# Power.net
KiCad netlist of a schematic drawn in Altium Designer
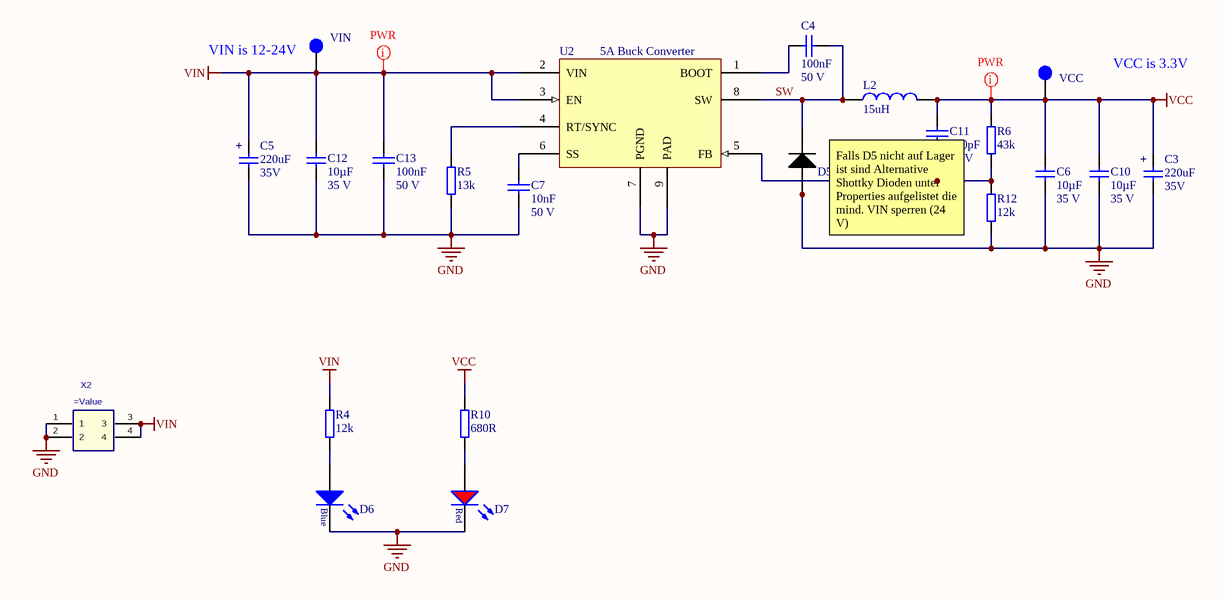
[diagram p0: Power.SchDoc]

(export (version "E")
  (design (tool "Eeschema 10.0.6"))
  (components
    (comp (ref "C3")
      (value "220uF")
      (footprint "CAPAE9083X105M")
      (description "ALUMINUM ELECTROLYTIC CAPACITOR")
      (fields
        (field (name "TOLERANCE") "20%")
        (field (name "LCSC PART #") "C311611")
        (field (name "VOLTAGE") "35V")
        (field (name "CREATED") "2018_06_25_AGeiger")
      )
      (libsource (lib "UZOhm_Optical") (part "C_ELKO_8x10"))
    )
    (comp (ref "C4")
      (value "100nF")
      (footprint "C_0603(1608)100_L")
      (description "CAP 0603 (1608 Metric) SMD")
      (fields
        (field (name "TOLERANCE") "±5%")
        (field (name "LCSC PART #") "C14663")
        (field (name "RATED VOLTAGE") "50 V")
        (field (name "CREATED") "2018_09_06_AGeiger")
      )
      (libsource (lib "UZOhm_Optical") (part "C_0603"))
    )
    (comp (ref "C5")
      (value "220uF")
      (footprint "CAPAE9083X105M")
      (description "ALUMINUM ELECTROLYTIC CAPACITOR")
      (fields
        (field (name "TOLERANCE") "20%")
        (field (name "LCSC PART #") "C311611")
        (field (name "VOLTAGE") "35V")
        (field (name "CREATED") "2018_06_25_AGeiger")
      )
      (libsource (lib "UZOhm_Optical") (part "C_ELKO_8x10"))
    )
    (comp (ref "C6")
      (value "10µF")
      (footprint "C_1206")
      (description "Capacitor 1206")
      (fields
        (field (name "TOLERANCE") "10%")
        (field (name "MF") "Taiyo Yuden")
        (field (name "VOLTAGE") "35 V")
        (field (name "CREATED") "2018_06_25_AGeiger")
      )
      (libsource (lib "UZOhm_Optical") (part "C_1206"))
    )
    (comp (ref "C7")
      (value "10nF")
      (footprint "C_0603(1608)100_L")
      (description "CAP 0603 (1608 Metric) SMD")
      (fields
        (field (name "TOLERANCE") "±5%")
        (field (name "LCSC PART #") "C57112")
        (field (name "RATED VOLTAGE") "50 V")
        (field (name "CREATED") "2018_09_06_AGeiger")
      )
      (libsource (lib "UZOhm_Optical") (part "C_0603"))
    )
    (comp (ref "C10")
      (value "10µF")
      (footprint "C_1206")
      (description "Capacitor 1206")
      (fields
        (field (name "TOLERANCE") "10%")
        (field (name "MF") "Taiyo Yuden")
        (field (name "VOLTAGE") "35 V")
        (field (name "CREATED") "2018_06_25_AGeiger")
      )
      (libsource (lib "UZOhm_Optical") (part "C_1206"))
    )
    (comp (ref "C11")
      (value "220pF")
      (footprint "C_0603(1608)100_L")
      (description "CAP 0603 (1608 Metric) SMD")
      (fields
        (field (name "TOLERANCE") "±5%")
        (field (name "LCSC PART #") "C1603")
        (field (name "RATED VOLTAGE") "50 V")
        (field (name "CREATED") "2018_09_06_AGeiger")
      )
      (libsource (lib "UZOhm_Optical") (part "C_0603"))
    )
    (comp (ref "C12")
      (value "10µF")
      (footprint "C_1206")
      (description "Capacitor 1206")
      (fields
        (field (name "TOLERANCE") "10%")
        (field (name "MF") "Taiyo Yuden")
        (field (name "VOLTAGE") "35 V")
        (field (name "CREATED") "2018_06_25_AGeiger")
      )
      (libsource (lib "UZOhm_Optical") (part "C_1206"))
    )
    (comp (ref "C13")
      (value "100nF")
      (footprint "C_0603(1608)100_L")
      (description "CAP 0603 (1608 Metric) SMD")
      (fields
        (field (name "TOLERANCE") "±5%")
        (field (name "LCSC PART #") "C14663")
        (field (name "RATED VOLTAGE") "50 V")
        (field (name "CREATED") "2018_09_06_AGeiger")
      )
      (libsource (lib "UZOhm_Optical") (part "C_0603"))
    )
    (comp (ref "D5")
      (value "~")
      (footprint "DPAK254P1542X460-3N")
      (description "SCHOTTKY BARRIER DIODES (SBD) TO-263-2 ROHS")
      (fields (field (name "LCSC PART #") "C181026"))
      (libsource (lib "UZOhm_Optical") (part "STPS30L60CG-TR"))
    )
    (comp (ref "D6")
      (value "150060BS75000")
      (footprint "WL-SMCW_0603")
      (description "WL-SMCW SMD Mono-color Chip LED Waterclear, size 0603, Blue, 3.2 V, 140°")
      (fields
        (field (name "MF") "Wuerth Elektronik")
        (field (name "LCSC PART #") "C72041")
        (field (name "CREATED") "2018_09_06_AGeiger")
      )
      (libsource (lib "UZOhm_Optical") (part "LED_Blue_0603"))
    )
    (comp (ref "D7")
      (value "150060RS75000")
      (footprint "WL-SMCW_0603")
      (description "WL-SMCW SMD Mono-color Chip LED Waterclear, size 0603, Red, 2 V, 140°")
      (fields
        (field (name "MF") "Wuerth Elektronik")
        (field (name "LCSC PART #") "C2286")
        (field (name "CREATED") "2018_09_06_AGeiger")
      )
      (libsource (lib "UZOhm_Optical") (part "LED_Red_0603"))
    )
    (comp (ref "L2")
      (value "15uH")
      (footprint "MWSA1004")
      (description "POWER INDUCTORS 2.2UH ±20% 13A SMD,10.5X11.5X4.0MM ROHS")
      (fields (field (name "LCSC PART #") "C151872"))
      (libsource (lib "UZOhm_Optical") (part "Inductor_2.2uH_13A"))
    )
    (comp (ref "R4")
      (value "12k")
      (footprint "R_0603_N")
      (description "SMD Resistor 0603")
      (fields
        (field (name "TOLERANCE") "1%")
        (field (name "VOLTAGE") "50V")
        (field (name "CREATED") "2018_09_06_AGeiger")
      )
      (libsource (lib "UZOhm_Optical") (part "R_0603_JLC"))
    )
    (comp (ref "R5")
      (value "13k")
      (footprint "R_0603_N")
      (description "SMD Resistor 0603")
      (fields
        (field (name "TOLERANCE") "1%")
        (field (name "VOLTAGE") "50V")
        (field (name "CREATED") "2018_09_06_AGeiger")
      )
      (libsource (lib "UZOhm_Optical") (part "R_0603_JLC"))
    )
    (comp (ref "R6")
      (value "43k")
      (footprint "R_0603_N")
      (description "SMD Resistor 0603")
      (fields
        (field (name "TOLERANCE") "1%")
        (field (name "VOLTAGE") "50V")
        (field (name "CREATED") "2018_09_06_AGeiger")
      )
      (libsource (lib "UZOhm_Optical") (part "R_0603_JLC"))
    )
    (comp (ref "R10")
      (value "680R")
      (footprint "R_0603_N")
      (description "SMD Resistor 0603")
      (fields
        (field (name "TOLERANCE") "1%")
        (field (name "VOLTAGE") "75V")
        (field (name "CREATED") "2018_09_06_AGeiger")
      )
      (libsource (lib "UZOhm_Optical") (part "R_0603"))
    )
    (comp (ref "R12")
      (value "12k")
      (footprint "R_0603_N")
      (description "SMD Resistor 0603")
      (fields
        (field (name "TOLERANCE") "1%")
        (field (name "VOLTAGE") "50V")
        (field (name "CREATED") "2018_09_06_AGeiger")
      )
      (libsource (lib "UZOhm_Optical") (part "R_0603_JLC"))
    )
    (comp (ref "U2")
      (value "5A Buck Converter")
      (footprint "SOP127P600X170_HS-9N")
      (description "SIMPLE SWITCHER® 40-V, 5-A, 2.2-MHz step-down converter with 40-μA IQr")
      (fields
        (field (name "MF") "Texas Instruments")
        (field (name "MPN") "LMR14050SDDAR")
        (field (name "CREATED") "2020_04_Kreppel")
      )
      (libsource (lib "UZOhm_Optical") (part "LMR14050"))
    )
    (comp (ref "VCC")
      (value "Testpoint 1mm")
      (footprint "TP_1mm")
      (fields (field (name "CREATED") "2018_06_25_AGeiger"))
      (libsource (lib "UZOhm_Optical") (part "TP_1mm"))
    )
    (comp (ref "VIN")
      (value "Testpoint 1mm")
      (footprint "TP_1mm")
      (fields (field (name "CREATED") "2018_06_25_AGeiger"))
      (libsource (lib "UZOhm_Optical") (part "TP_1mm"))
    )
    (comp (ref "X2")
      (value "~")
      (footprint "IPL1-102-01-L-D-K")
      (description "2.54mm Double Row Terminal Assembly, Right-Angled")
      (fields (field (name "MANUFACTURER") "SAMTEC") (field (name "CREATED") "2018_05_02_AGeiger"))
      (libsource (lib "UZOhm_Optical") (part "IPL1-102-XX-X-D-X"))
    )
  )
  (nets
    (net (code "1") (name "/SW") (class "Default")
      (node (ref "C4") (pin "2") (pinfunction "2_2") (pintype "passive"))
      (node (ref "D5") (pin "4") (pinfunction "K_4") (pintype "passive"))
      (node (ref "L2") (pin "1") (pinfunction "1_1") (pintype "passive"))
      (node (ref "U2") (pin "8") (pinfunction "SW_8") (pintype "power_in"))
    )
    (net (code "2") (name "GND") (class "Default")
      (node (ref "C10") (pin "1") (pinfunction "1_1") (pintype "passive"))
      (node (ref "C12") (pin "1") (pinfunction "1_1") (pintype "passive"))
      (node (ref "C13") (pin "1") (pinfunction "1_1") (pintype "passive"))
      (node (ref "C3") (pin "2") (pinfunction "2_2") (pintype "passive"))
      (node (ref "C5") (pin "2") (pinfunction "2_2") (pintype "passive"))
      (node (ref "C6") (pin "1") (pinfunction "1_1") (pintype "passive"))
      (node (ref "C7") (pin "2") (pinfunction "2_2") (pintype "passive"))
      (node (ref "D5") (pin "1") (pinfunction "A_1") (pintype "passive"))
      (node (ref "D5") (pin "3") (pinfunction "A_3") (pintype "passive"))
      (node (ref "D6") (pin "1") (pinfunction "K_1") (pintype "passive"))
      (node (ref "D7") (pin "1") (pinfunction "K_1") (pintype "passive"))
      (node (ref "R12") (pin "1") (pinfunction "1_1") (pintype "passive"))
      (node (ref "R5") (pin "1") (pinfunction "1_1") (pintype "passive"))
      (node (ref "U2") (pin "7") (pinfunction "PGND_7") (pintype "power_in"))
      (node (ref "U2") (pin "9") (pinfunction "PAD_9") (pintype "power_in"))
      (node (ref "X2") (pin "1") (pinfunction "1_1") (pintype "passive"))
      (node (ref "X2") (pin "2") (pinfunction "2_2") (pintype "passive"))
    )
    (net (code "3") (name "Net-(D6-A)") (class "Default")
      (node (ref "D6") (pin "2") (pinfunction "A_2") (pintype "passive"))
      (node (ref "R4") (pin "1") (pinfunction "1_1") (pintype "passive"))
    )
    (net (code "4") (name "Net-(D7-A)") (class "Default")
      (node (ref "D7") (pin "2") (pinfunction "A_2") (pintype "passive"))
      (node (ref "R10") (pin "1") (pinfunction "1_1") (pintype "passive"))
    )
    (net (code "5") (name "Net-(U2-BOOT)") (class "Default")
      (node (ref "C4") (pin "1") (pinfunction "1_1") (pintype "passive"))
      (node (ref "U2") (pin "1") (pinfunction "BOOT_1") (pintype "power_in"))
    )
    (net (code "6") (name "Net-(U2-FB)") (class "Default")
      (node (ref "C11") (pin "2") (pinfunction "2_2") (pintype "passive"))
      (node (ref "R12") (pin "2") (pinfunction "2_2") (pintype "passive"))
      (node (ref "R6") (pin "1") (pinfunction "1_1") (pintype "passive"))
      (node (ref "U2") (pin "5") (pinfunction "FB_5") (pintype "input"))
    )
    (net (code "7") (name "Net-(U2-RT{slash}SYNC)") (class "Default")
      (node (ref "R5") (pin "2") (pinfunction "2_2") (pintype "passive"))
      (node (ref "U2") (pin "4") (pinfunction "RT/SYNC_4") (pintype "passive"))
    )
    (net (code "8") (name "Net-(U2-SS)") (class "Default")
      (node (ref "C7") (pin "1") (pinfunction "1_1") (pintype "passive"))
      (node (ref "U2") (pin "6") (pinfunction "SS_6") (pintype "power_in"))
    )
    (net (code "9") (name "VCC") (class "Default")
      (node (ref "C10") (pin "2") (pinfunction "2_2") (pintype "passive"))
      (node (ref "C11") (pin "1") (pinfunction "1_1") (pintype "passive"))
      (node (ref "C3") (pin "1") (pinfunction "1_1") (pintype "passive"))
      (node (ref "C6") (pin "2") (pinfunction "2_2") (pintype "passive"))
      (node (ref "L2") (pin "2") (pinfunction "2_2") (pintype "passive"))
      (node (ref "R10") (pin "2") (pinfunction "2_2") (pintype "passive"))
      (node (ref "R6") (pin "2") (pinfunction "2_2") (pintype "passive"))
      (node (ref "VCC") (pin "1") (pintype "passive"))
    )
    (net (code "10") (name "VIN") (class "Default")
      (node (ref "C12") (pin "2") (pinfunction "2_2") (pintype "passive"))
      (node (ref "C13") (pin "2") (pinfunction "2_2") (pintype "passive"))
      (node (ref "C5") (pin "1") (pinfunction "1_1") (pintype "passive"))
      (node (ref "R4") (pin "2") (pinfunction "2_2") (pintype "passive"))
      (node (ref "U2") (pin "2") (pinfunction "VIN_2") (pintype "power_in"))
      (node (ref "U2") (pin "3") (pinfunction "EN_3") (pintype "input"))
      (node (ref "VIN") (pin "1") (pintype "passive"))
      (node (ref "X2") (pin "3") (pinfunction "3_3") (pintype "passive"))
      (node (ref "X2") (pin "4") (pinfunction "4_4") (pintype "passive"))
    )
  )
)
